# panda_debug.net
KiCad netlist of a schematic drawn in EAGLE
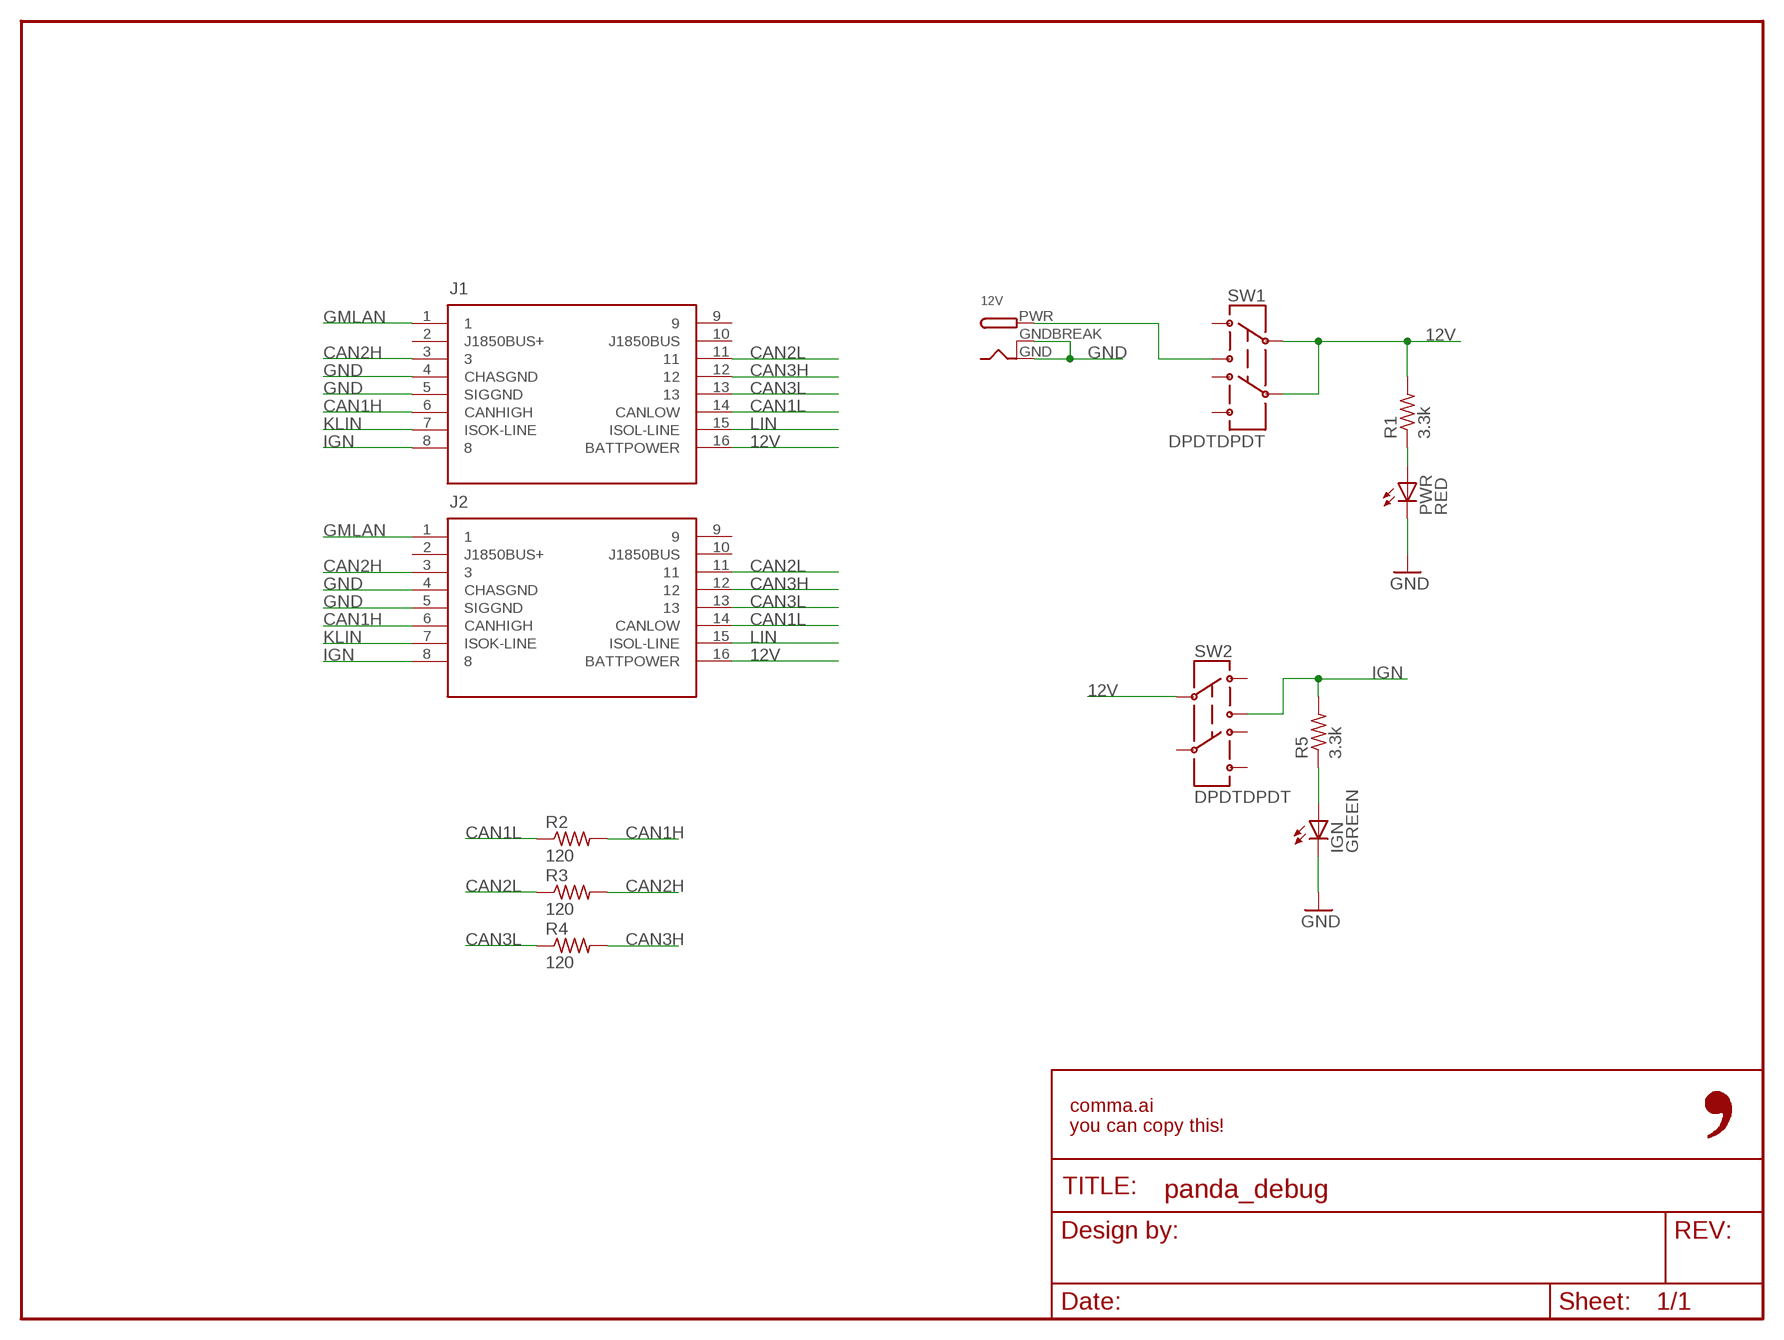
[diagram p0: schematic, sheet 1]

(export (version "E")
  (design (tool "Eeschema 10.0.6"))
  (components
    (comp (ref "12V")
      (value "DCBARRELPTH")
      (footprint "eagle-import:DCJACK_2MM_PTH")
      (libsource (lib "eagle-import") (part "DCBARRELPTH"))
    )
    (comp (ref "FRAME1")
      (value "FRAME-LETTER-OPENNO_PACKAGE")
      (footprint "eagle-import:DUMMY")
      (fields (field (name "DESIGNER") "Nobody"))
      (libsource (lib "eagle-import") (part "FRAME-LETTER-OPENNO_PACKAGE"))
    )
    (comp (ref "IGN")
      (value "GREEN")
      (footprint "eagle-import:CHIPLED_0805")
      (libsource (lib "eagle-import") (part "LEDCHIPLED_0805"))
    )
    (comp (ref "J1")
      (value "OBDII-FEMALEFEMALE")
      (footprint "eagle-import:OBDII-FEMALE")
      (libsource (lib "eagle-import") (part "OBDII-FEMALEFEMALE"))
    )
    (comp (ref "J2")
      (value "OBDII-FEMALEFEMALE")
      (footprint "eagle-import:OBDII-FEMALE")
      (libsource (lib "eagle-import") (part "OBDII-FEMALEFEMALE"))
    )
    (comp (ref "PWR")
      (value "RED")
      (footprint "eagle-import:CHIPLED_0805")
      (libsource (lib "eagle-import") (part "LEDCHIPLED_0805"))
    )
    (comp (ref "R1")
      (value "3.3k")
      (footprint "eagle-import:0603-R")
      (libsource (lib "eagle-import") (part "R0603"))
    )
    (comp (ref "R2")
      (value "120")
      (footprint "eagle-import:0603-R")
      (libsource (lib "eagle-import") (part "R0603"))
    )
    (comp (ref "R3")
      (value "120")
      (footprint "eagle-import:0603-R")
      (libsource (lib "eagle-import") (part "R0603"))
    )
    (comp (ref "R4")
      (value "120")
      (footprint "eagle-import:0603-R")
      (libsource (lib "eagle-import") (part "R0603"))
    )
    (comp (ref "R5")
      (value "3.3k")
      (footprint "eagle-import:0603-R")
      (libsource (lib "eagle-import") (part "R0603"))
    )
    (comp (ref "SW1")
      (value "DPDTDPDT")
      (footprint "eagle-import:AYZ0202")
      (libsource (lib "eagle-import") (part "DPDTDPDT"))
    )
    (comp (ref "SW2")
      (value "DPDTDPDT")
      (footprint "eagle-import:AYZ0202")
      (libsource (lib "eagle-import") (part "DPDTDPDT"))
    )
  )
  (nets
    (net (code "1") (name "/12V") (class "Default")
      (node (ref "J1") (pin "16") (pinfunction "BATTPOWER_16") (pintype "bidirectional"))
      (node (ref "J2") (pin "16") (pinfunction "BATTPOWER_16") (pintype "bidirectional"))
      (node (ref "R1") (pin "2") (pinfunction "2_2") (pintype "passive"))
      (node (ref "SW1") (pin "2") (pinfunction "2_2") (pintype "bidirectional"))
      (node (ref "SW1") (pin "5") (pinfunction "5_5") (pintype "bidirectional"))
      (node (ref "SW2") (pin "2") (pinfunction "2_2") (pintype "bidirectional"))
    )
    (net (code "2") (name "/CAN1H") (class "Default")
      (node (ref "J1") (pin "6") (pinfunction "CANHIGH_6") (pintype "bidirectional"))
      (node (ref "J2") (pin "6") (pinfunction "CANHIGH_6") (pintype "bidirectional"))
      (node (ref "R2") (pin "2") (pinfunction "2_2") (pintype "passive"))
    )
    (net (code "3") (name "/CAN1L") (class "Default")
      (node (ref "J1") (pin "14") (pinfunction "CANLOW_14") (pintype "bidirectional"))
      (node (ref "J2") (pin "14") (pinfunction "CANLOW_14") (pintype "bidirectional"))
      (node (ref "R2") (pin "1") (pinfunction "1_1") (pintype "passive"))
    )
    (net (code "4") (name "/CAN2H") (class "Default")
      (node (ref "J1") (pin "3") (pinfunction "3_3") (pintype "bidirectional"))
      (node (ref "J2") (pin "3") (pinfunction "3_3") (pintype "bidirectional"))
      (node (ref "R3") (pin "2") (pinfunction "2_2") (pintype "passive"))
    )
    (net (code "5") (name "/CAN2L") (class "Default")
      (node (ref "J1") (pin "11") (pinfunction "11_11") (pintype "bidirectional"))
      (node (ref "J2") (pin "11") (pinfunction "11_11") (pintype "bidirectional"))
      (node (ref "R3") (pin "1") (pinfunction "1_1") (pintype "passive"))
    )
    (net (code "6") (name "/CAN3H") (class "Default")
      (node (ref "J1") (pin "12") (pinfunction "12_12") (pintype "bidirectional"))
      (node (ref "J2") (pin "12") (pinfunction "12_12") (pintype "bidirectional"))
      (node (ref "R4") (pin "2") (pinfunction "2_2") (pintype "passive"))
    )
    (net (code "7") (name "/CAN3L") (class "Default")
      (node (ref "J1") (pin "13") (pinfunction "13_13") (pintype "bidirectional"))
      (node (ref "J2") (pin "13") (pinfunction "13_13") (pintype "bidirectional"))
      (node (ref "R4") (pin "1") (pinfunction "1_1") (pintype "passive"))
    )
    (net (code "8") (name "/GMLAN") (class "Default")
      (node (ref "J1") (pin "1") (pinfunction "1_1") (pintype "bidirectional"))
      (node (ref "J2") (pin "1") (pinfunction "1_1") (pintype "bidirectional"))
    )
    (net (code "9") (name "/IGN") (class "Default")
      (node (ref "J1") (pin "8") (pinfunction "8_8") (pintype "bidirectional"))
      (node (ref "J2") (pin "8") (pinfunction "8_8") (pintype "bidirectional"))
      (node (ref "R5") (pin "2") (pinfunction "2_2") (pintype "passive"))
      (node (ref "SW2") (pin "3") (pinfunction "3_3") (pintype "bidirectional"))
    )
    (net (code "10") (name "/KLIN") (class "Default")
      (node (ref "J1") (pin "7") (pinfunction "ISOK-LINE_7") (pintype "bidirectional"))
      (node (ref "J2") (pin "7") (pinfunction "ISOK-LINE_7") (pintype "bidirectional"))
    )
    (net (code "11") (name "/LIN") (class "Default")
      (node (ref "J1") (pin "15") (pinfunction "ISOL-LINE_15") (pintype "bidirectional"))
      (node (ref "J2") (pin "15") (pinfunction "ISOL-LINE_15") (pintype "bidirectional"))
    )
    (net (code "12") (name "GND") (class "Default")
      (node (ref "12V") (pin "GND") (pinfunction "GND_GND") (pintype "power_in"))
      (node (ref "12V") (pin "GNDBREAK") (pinfunction "GNDBREAK_GNDBREAK") (pintype "power_in"))
      (node (ref "IGN") (pin "C") (pinfunction "C_C") (pintype "passive"))
      (node (ref "J1") (pin "4") (pinfunction "CHASGND_4") (pintype "bidirectional"))
      (node (ref "J1") (pin "5") (pinfunction "SIGGND_5") (pintype "bidirectional"))
      (node (ref "J2") (pin "4") (pinfunction "CHASGND_4") (pintype "bidirectional"))
      (node (ref "J2") (pin "5") (pinfunction "SIGGND_5") (pintype "bidirectional"))
      (node (ref "PWR") (pin "C") (pinfunction "C_C") (pintype "passive"))
    )
    (net (code "13") (name "Net-(12V-PadPWR)") (class "Default")
      (node (ref "12V") (pin "PWR") (pinfunction "PWR_PWR") (pintype "power_in"))
      (node (ref "SW1") (pin "3") (pinfunction "3_3") (pintype "bidirectional"))
    )
    (net (code "14") (name "Net-(IGN-PadA)") (class "Default")
      (node (ref "IGN") (pin "A") (pinfunction "A_A") (pintype "passive"))
      (node (ref "R5") (pin "1") (pinfunction "1_1") (pintype "passive"))
    )
    (net (code "15") (name "Net-(PWR-PadA)") (class "Default")
      (node (ref "PWR") (pin "A") (pinfunction "A_A") (pintype "passive"))
      (node (ref "R1") (pin "1") (pinfunction "1_1") (pintype "passive"))
    )
    (net (code "16") (name "unconnected-(J1-J1850BUS+-Pad2)") (class "Default")
      (node (ref "J1") (pin "2") (pinfunction "J1850BUS+_2") (pintype "bidirectional"))
    )
    (net (code "17") (name "unconnected-(J1-J1850BUS-Pad10)") (class "Default")
      (node (ref "J1") (pin "10") (pinfunction "J1850BUS_10") (pintype "bidirectional"))
    )
    (net (code "18") (name "unconnected-(J1-Pad9)") (class "Default")
      (node (ref "J1") (pin "9") (pinfunction "9_9") (pintype "bidirectional"))
    )
    (net (code "19") (name "unconnected-(J2-J1850BUS+-Pad2)") (class "Default")
      (node (ref "J2") (pin "2") (pinfunction "J1850BUS+_2") (pintype "bidirectional"))
    )
    (net (code "20") (name "unconnected-(J2-J1850BUS-Pad10)") (class "Default")
      (node (ref "J2") (pin "10") (pinfunction "J1850BUS_10") (pintype "bidirectional"))
    )
    (net (code "21") (name "unconnected-(J2-Pad9)") (class "Default")
      (node (ref "J2") (pin "9") (pinfunction "9_9") (pintype "bidirectional"))
    )
    (net (code "22") (name "unconnected-(SW1-Pad1)") (class "Default")
      (node (ref "SW1") (pin "1") (pinfunction "1_1") (pintype "bidirectional"))
    )
    (net (code "23") (name "unconnected-(SW1-Pad4)") (class "Default")
      (node (ref "SW1") (pin "4") (pinfunction "4_4") (pintype "bidirectional"))
    )
    (net (code "24") (name "unconnected-(SW1-Pad6)") (class "Default")
      (node (ref "SW1") (pin "6") (pinfunction "6_6") (pintype "bidirectional"))
    )
    (net (code "25") (name "unconnected-(SW2-Pad1)") (class "Default")
      (node (ref "SW2") (pin "1") (pinfunction "1_1") (pintype "bidirectional"))
    )
    (net (code "26") (name "unconnected-(SW2-Pad4)") (class "Default")
      (node (ref "SW2") (pin "4") (pinfunction "4_4") (pintype "bidirectional"))
    )
    (net (code "27") (name "unconnected-(SW2-Pad5)") (class "Default")
      (node (ref "SW2") (pin "5") (pinfunction "5_5") (pintype "bidirectional"))
    )
    (net (code "28") (name "unconnected-(SW2-Pad6)") (class "Default")
      (node (ref "SW2") (pin "6") (pinfunction "6_6") (pintype "bidirectional"))
    )
  )
)
